# BLOCK7.net
KiCad netlist of a schematic drawn in Altium Designer
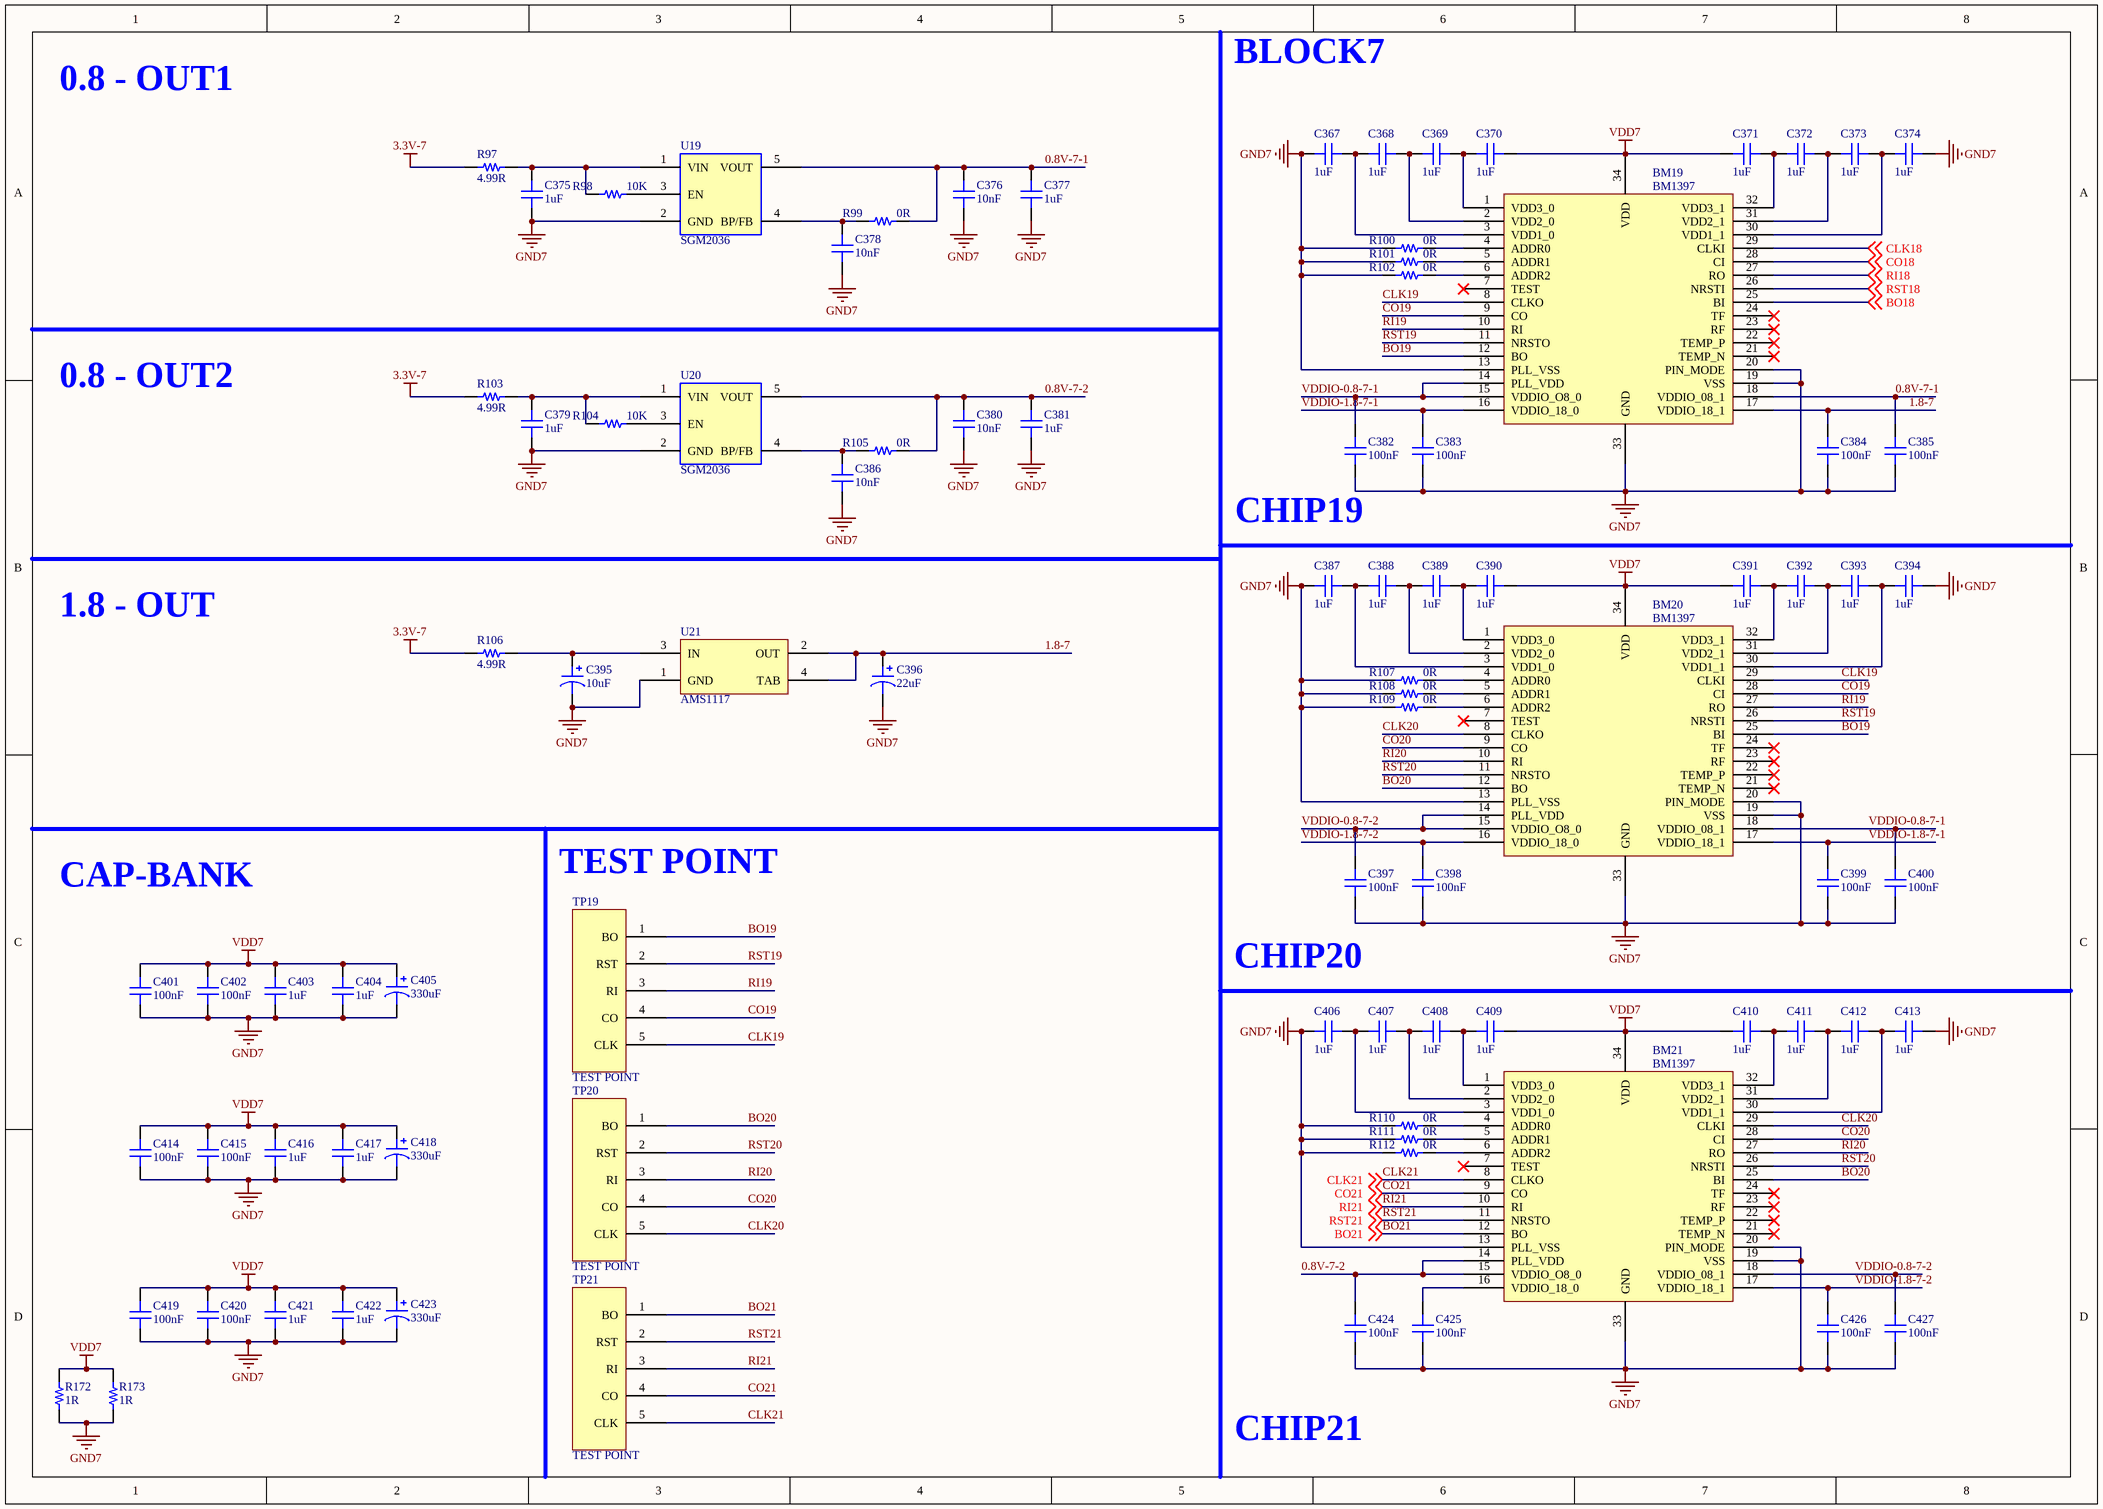
[diagram p0: BLOCK7.SchDoc]

(export (version "E")
  (design (tool "Eeschema 10.0.6"))
  (components
    (comp (ref "BM19") (value "BM1397") (footprint "BM1387") (libsource (lib "Miner_8TH") (part "BM1397_0")))
    (comp (ref "BM20") (value "BM1397") (footprint "BM1387") (libsource (lib "Miner_8TH") (part "BM1397_0")))
    (comp (ref "BM21") (value "BM1397") (footprint "BM1387") (libsource (lib "Miner_8TH") (part "BM1397_0")))
    (comp (ref "C367") (value "1uF") (footprint "CAP-SMD-0603") (libsource (lib "Miner_8TH") (part "CAP")))
    (comp (ref "C368") (value "1uF") (footprint "CAP-SMD-0603") (libsource (lib "Miner_8TH") (part "CAP")))
    (comp (ref "C369") (value "1uF") (footprint "CAP-SMD-0603") (libsource (lib "Miner_8TH") (part "CAP")))
    (comp (ref "C370") (value "1uF") (footprint "CAP-SMD-0603") (libsource (lib "Miner_8TH") (part "CAP")))
    (comp (ref "C371") (value "1uF") (footprint "CAP-SMD-0603") (libsource (lib "Miner_8TH") (part "CAP")))
    (comp (ref "C372") (value "1uF") (footprint "CAP-SMD-0603") (libsource (lib "Miner_8TH") (part "CAP")))
    (comp (ref "C373") (value "1uF") (footprint "CAP-SMD-0603") (libsource (lib "Miner_8TH") (part "CAP")))
    (comp (ref "C374") (value "1uF") (footprint "CAP-SMD-0603") (libsource (lib "Miner_8TH") (part "CAP")))
    (comp (ref "C375") (value "1uF") (footprint "CAP_SMD_0805") (libsource (lib "Miner_8TH") (part "CAP")))
    (comp (ref "C376") (value "10nF") (footprint "CAP_SMD_0805") (libsource (lib "Miner_8TH") (part "CAP")))
    (comp (ref "C377") (value "1uF") (footprint "CAP_SMD_0805") (libsource (lib "Miner_8TH") (part "CAP")))
    (comp (ref "C378") (value "10nF") (footprint "CAP_SMD_0805") (libsource (lib "Miner_8TH") (part "CAP")))
    (comp (ref "C379") (value "1uF") (footprint "CAP_SMD_0805") (libsource (lib "Miner_8TH") (part "CAP")))
    (comp (ref "C380") (value "10nF") (footprint "CAP_SMD_0805") (libsource (lib "Miner_8TH") (part "CAP")))
    (comp (ref "C381") (value "1uF") (footprint "CAP_SMD_0805") (libsource (lib "Miner_8TH") (part "CAP")))
    (comp (ref "C382") (value "100nF") (footprint "CAP_SMD_0805") (libsource (lib "Miner_8TH") (part "CAP")))
    (comp (ref "C383") (value "100nF") (footprint "CAP_SMD_0805") (libsource (lib "Miner_8TH") (part "CAP")))
    (comp (ref "C384") (value "100nF") (footprint "CAP_SMD_0805") (libsource (lib "Miner_8TH") (part "CAP")))
    (comp (ref "C385") (value "100nF") (footprint "CAP_SMD_0805") (libsource (lib "Miner_8TH") (part "CAP")))
    (comp (ref "C386") (value "10nF") (footprint "CAP_SMD_0805") (libsource (lib "Miner_8TH") (part "CAP")))
    (comp (ref "C387") (value "1uF") (footprint "CAP-SMD-0603") (libsource (lib "Miner_8TH") (part "CAP")))
    (comp (ref "C388") (value "1uF") (footprint "CAP-SMD-0603") (libsource (lib "Miner_8TH") (part "CAP")))
    (comp (ref "C389") (value "1uF") (footprint "CAP-SMD-0603") (libsource (lib "Miner_8TH") (part "CAP")))
    (comp (ref "C390") (value "1uF") (footprint "CAP-SMD-0603") (libsource (lib "Miner_8TH") (part "CAP")))
    (comp (ref "C391") (value "1uF") (footprint "CAP-SMD-0603") (libsource (lib "Miner_8TH") (part "CAP")))
    (comp (ref "C392") (value "1uF") (footprint "CAP-SMD-0603") (libsource (lib "Miner_8TH") (part "CAP")))
    (comp (ref "C393") (value "1uF") (footprint "CAP-SMD-0603") (libsource (lib "Miner_8TH") (part "CAP")))
    (comp (ref "C394") (value "1uF") (footprint "CAP-SMD-0603") (libsource (lib "Miner_8TH") (part "CAP")))
    (comp (ref "C395")
      (value "10uF")
      (footprint "CAP-TAN-CASE-A")
      (libsource (lib "Miner_8TH") (part "POLARIZED CAP"))
    )
    (comp (ref "C396")
      (value "22uF")
      (footprint "CAP-TAN-CASE-A")
      (libsource (lib "Miner_8TH") (part "POLARIZED CAP"))
    )
    (comp (ref "C397") (value "100nF") (footprint "CAP_SMD_0805") (libsource (lib "Miner_8TH") (part "CAP")))
    (comp (ref "C398") (value "100nF") (footprint "CAP_SMD_0805") (libsource (lib "Miner_8TH") (part "CAP")))
    (comp (ref "C399") (value "100nF") (footprint "CAP_SMD_0805") (libsource (lib "Miner_8TH") (part "CAP")))
    (comp (ref "C400") (value "100nF") (footprint "CAP_SMD_0805") (libsource (lib "Miner_8TH") (part "CAP")))
    (comp (ref "C401") (value "100nF") (footprint "CAP_SMD_0805") (libsource (lib "Miner_8TH") (part "CAP")))
    (comp (ref "C402") (value "100nF") (footprint "CAP_SMD_0805") (libsource (lib "Miner_8TH") (part "CAP")))
    (comp (ref "C403") (value "1uF") (footprint "CAP_SMD_0805") (libsource (lib "Miner_8TH") (part "CAP")))
    (comp (ref "C404") (value "1uF") (footprint "CAP_SMD_0805") (libsource (lib "Miner_8TH") (part "CAP")))
    (comp (ref "C405")
      (value "330uF")
      (footprint "CAP-TAN-CASE-E")
      (libsource (lib "Miner_8TH") (part "POLARIZED CAP"))
    )
    (comp (ref "C406") (value "1uF") (footprint "CAP-SMD-0603") (libsource (lib "Miner_8TH") (part "CAP")))
    (comp (ref "C407") (value "1uF") (footprint "CAP-SMD-0603") (libsource (lib "Miner_8TH") (part "CAP")))
    (comp (ref "C408") (value "1uF") (footprint "CAP-SMD-0603") (libsource (lib "Miner_8TH") (part "CAP")))
    (comp (ref "C409") (value "1uF") (footprint "CAP-SMD-0603") (libsource (lib "Miner_8TH") (part "CAP")))
    (comp (ref "C410") (value "1uF") (footprint "CAP-SMD-0603") (libsource (lib "Miner_8TH") (part "CAP")))
    (comp (ref "C411") (value "1uF") (footprint "CAP-SMD-0603") (libsource (lib "Miner_8TH") (part "CAP")))
    (comp (ref "C412") (value "1uF") (footprint "CAP-SMD-0603") (libsource (lib "Miner_8TH") (part "CAP")))
    (comp (ref "C413") (value "1uF") (footprint "CAP-SMD-0603") (libsource (lib "Miner_8TH") (part "CAP")))
    (comp (ref "C414") (value "100nF") (footprint "CAP_SMD_0805") (libsource (lib "Miner_8TH") (part "CAP")))
    (comp (ref "C415") (value "100nF") (footprint "CAP_SMD_0805") (libsource (lib "Miner_8TH") (part "CAP")))
    (comp (ref "C416") (value "1uF") (footprint "CAP_SMD_0805") (libsource (lib "Miner_8TH") (part "CAP")))
    (comp (ref "C417") (value "1uF") (footprint "CAP_SMD_0805") (libsource (lib "Miner_8TH") (part "CAP")))
    (comp (ref "C418")
      (value "330uF")
      (footprint "CAP-TAN-CASE-E")
      (libsource (lib "Miner_8TH") (part "POLARIZED CAP"))
    )
    (comp (ref "C419") (value "100nF") (footprint "CAP_SMD_0805") (libsource (lib "Miner_8TH") (part "CAP")))
    (comp (ref "C420") (value "100nF") (footprint "CAP_SMD_0805") (libsource (lib "Miner_8TH") (part "CAP")))
    (comp (ref "C421") (value "1uF") (footprint "CAP_SMD_0805") (libsource (lib "Miner_8TH") (part "CAP")))
    (comp (ref "C422") (value "1uF") (footprint "CAP_SMD_0805") (libsource (lib "Miner_8TH") (part "CAP")))
    (comp (ref "C423")
      (value "330uF")
      (footprint "CAP-TAN-CASE-E")
      (libsource (lib "Miner_8TH") (part "POLARIZED CAP"))
    )
    (comp (ref "C424") (value "100nF") (footprint "CAP_SMD_0805") (libsource (lib "Miner_8TH") (part "CAP")))
    (comp (ref "C425") (value "100nF") (footprint "CAP_SMD_0805") (libsource (lib "Miner_8TH") (part "CAP")))
    (comp (ref "C426") (value "100nF") (footprint "CAP_SMD_0805") (libsource (lib "Miner_8TH") (part "CAP")))
    (comp (ref "C427") (value "100nF") (footprint "CAP_SMD_0805") (libsource (lib "Miner_8TH") (part "CAP")))
    (comp (ref "R97") (value "4.99R") (footprint "RES-SMD-1206") (libsource (lib "Miner_8TH") (part "RES")))
    (comp (ref "R98") (value "10K") (footprint "RES-SMD-0402") (libsource (lib "Miner_8TH") (part "RES")))
    (comp (ref "R99") (value "0R") (footprint "RES-SMD-0402") (libsource (lib "Miner_8TH") (part "RES")))
    (comp (ref "R100") (value "0R") (footprint "RES-SMD-0402") (libsource (lib "Miner_8TH") (part "RES")))
    (comp (ref "R101") (value "0R") (footprint "RES-SMD-0402") (libsource (lib "Miner_8TH") (part "RES")))
    (comp (ref "R102") (value "0R") (footprint "RES-SMD-0402") (libsource (lib "Miner_8TH") (part "RES")))
    (comp (ref "R103") (value "4.99R") (footprint "RES-SMD-1206") (libsource (lib "Miner_8TH") (part "RES")))
    (comp (ref "R104") (value "10K") (footprint "RES-SMD-0402") (libsource (lib "Miner_8TH") (part "RES")))
    (comp (ref "R105") (value "0R") (footprint "RES-SMD-0402") (libsource (lib "Miner_8TH") (part "RES")))
    (comp (ref "R106") (value "4.99R") (footprint "RES-SMD-1206") (libsource (lib "Miner_8TH") (part "RES")))
    (comp (ref "R107") (value "0R") (footprint "RES-SMD-0402") (libsource (lib "Miner_8TH") (part "RES")))
    (comp (ref "R108") (value "0R") (footprint "RES-SMD-0402") (libsource (lib "Miner_8TH") (part "RES")))
    (comp (ref "R109") (value "0R") (footprint "RES-SMD-0402") (libsource (lib "Miner_8TH") (part "RES")))
    (comp (ref "R110") (value "0R") (footprint "RES-SMD-0402") (libsource (lib "Miner_8TH") (part "RES")))
    (comp (ref "R111") (value "0R") (footprint "RES-SMD-0402") (libsource (lib "Miner_8TH") (part "RES")))
    (comp (ref "R112") (value "0R") (footprint "RES-SMD-0402") (libsource (lib "Miner_8TH") (part "RES")))
    (comp (ref "R172") (value "1R") (footprint "RES-SMD-1210") (libsource (lib "Miner_8TH") (part "RES")))
    (comp (ref "R173") (value "1R") (footprint "RES-SMD-1210") (libsource (lib "Miner_8TH") (part "RES")))
    (comp (ref "TP19")
      (value "TEST POINT")
      (footprint "TEST_POINT")
      (libsource (lib "Miner_8TH") (part "TEST POINT"))
    )
    (comp (ref "TP20")
      (value "TEST POINT")
      (footprint "TEST_POINT")
      (libsource (lib "Miner_8TH") (part "TEST POINT"))
    )
    (comp (ref "TP21")
      (value "TEST POINT")
      (footprint "TEST_POINT")
      (libsource (lib "Miner_8TH") (part "TEST POINT"))
    )
    (comp (ref "U19")
      (value "SGM2036")
      (footprint "SOT23-5PIN")
      (libsource (lib "Miner_8TH") (part "SGM2036"))
    )
    (comp (ref "U20")
      (value "SGM2036")
      (footprint "SOT23-5PIN")
      (libsource (lib "Miner_8TH") (part "SGM2036"))
    )
    (comp (ref "U21") (value "AMS1117") (footprint "AMS1117") (libsource (lib "Miner_8TH") (part "AMS1117")))
  )
  (nets
    (net (code "1") (name "/0.8V-7-1") (class "Default")
      (node (ref "BM19") (pin "18") (pinfunction "VDDIO_08_1_18") (pintype "passive"))
      (node (ref "C376") (pin "2") (pinfunction "2_2") (pintype "passive"))
      (node (ref "C377") (pin "2") (pinfunction "2_2") (pintype "passive"))
      (node (ref "C385") (pin "2") (pinfunction "2_2") (pintype "passive"))
      (node (ref "R99") (pin "2") (pinfunction "2_2") (pintype "passive"))
      (node (ref "U19") (pin "5") (pinfunction "VOUT_5") (pintype "passive"))
    )
    (net (code "2") (name "/0.8V-7-2") (class "Default")
      (node (ref "BM21") (pin "14") (pinfunction "PLL_VDD_14") (pintype "passive"))
      (node (ref "BM21") (pin "15") (pinfunction "VDDIO_O8_0_15") (pintype "passive"))
      (node (ref "C380") (pin "2") (pinfunction "2_2") (pintype "passive"))
      (node (ref "C381") (pin "2") (pinfunction "2_2") (pintype "passive"))
      (node (ref "C424") (pin "2") (pinfunction "2_2") (pintype "passive"))
      (node (ref "R105") (pin "2") (pinfunction "2_2") (pintype "passive"))
      (node (ref "U20") (pin "5") (pinfunction "VOUT_5") (pintype "passive"))
    )
    (net (code "3") (name "/1.8-7") (class "Default")
      (node (ref "BM19") (pin "17") (pinfunction "VDDIO_18_1_17") (pintype "passive"))
      (node (ref "C384") (pin "2") (pinfunction "2_2") (pintype "passive"))
      (node (ref "C396") (pin "1") (pinfunction "1_1") (pintype "passive"))
      (node (ref "U21") (pin "2") (pinfunction "OUT_2") (pintype "passive"))
      (node (ref "U21") (pin "4") (pinfunction "TAB_4") (pintype "passive"))
    )
    (net (code "4") (name "/BO19") (class "Default")
      (node (ref "BM19") (pin "12") (pinfunction "BO_12") (pintype "passive"))
      (node (ref "BM20") (pin "25") (pinfunction "BI_25") (pintype "passive"))
      (node (ref "TP19") (pin "1") (pinfunction "BO_1") (pintype "passive"))
    )
    (net (code "5") (name "/BO20") (class "Default")
      (node (ref "BM20") (pin "12") (pinfunction "BO_12") (pintype "passive"))
      (node (ref "BM21") (pin "25") (pinfunction "BI_25") (pintype "passive"))
      (node (ref "TP20") (pin "1") (pinfunction "BO_1") (pintype "passive"))
    )
    (net (code "6") (name "/CLK19") (class "Default")
      (node (ref "BM19") (pin "8") (pinfunction "CLKO_8") (pintype "passive"))
      (node (ref "BM20") (pin "29") (pinfunction "CLKI_29") (pintype "passive"))
      (node (ref "TP19") (pin "5") (pinfunction "CLK_5") (pintype "passive"))
    )
    (net (code "7") (name "/CLK20") (class "Default")
      (node (ref "BM20") (pin "8") (pinfunction "CLKO_8") (pintype "passive"))
      (node (ref "BM21") (pin "29") (pinfunction "CLKI_29") (pintype "passive"))
      (node (ref "TP20") (pin "5") (pinfunction "CLK_5") (pintype "passive"))
    )
    (net (code "8") (name "/CO19") (class "Default")
      (node (ref "BM19") (pin "9") (pinfunction "CO_9") (pintype "passive"))
      (node (ref "BM20") (pin "28") (pinfunction "CI_28") (pintype "passive"))
      (node (ref "TP19") (pin "4") (pinfunction "CO_4") (pintype "passive"))
    )
    (net (code "9") (name "/CO20") (class "Default")
      (node (ref "BM20") (pin "9") (pinfunction "CO_9") (pintype "passive"))
      (node (ref "BM21") (pin "28") (pinfunction "CI_28") (pintype "passive"))
      (node (ref "TP20") (pin "4") (pinfunction "CO_4") (pintype "passive"))
    )
    (net (code "10") (name "/RI19") (class "Default")
      (node (ref "BM19") (pin "10") (pinfunction "RI_10") (pintype "passive"))
      (node (ref "BM20") (pin "27") (pinfunction "RO_27") (pintype "passive"))
      (node (ref "TP19") (pin "3") (pinfunction "RI_3") (pintype "passive"))
    )
    (net (code "11") (name "/RI20") (class "Default")
      (node (ref "BM20") (pin "10") (pinfunction "RI_10") (pintype "passive"))
      (node (ref "BM21") (pin "27") (pinfunction "RO_27") (pintype "passive"))
      (node (ref "TP20") (pin "3") (pinfunction "RI_3") (pintype "passive"))
    )
    (net (code "12") (name "/RST19") (class "Default")
      (node (ref "BM19") (pin "11") (pinfunction "NRSTO_11") (pintype "passive"))
      (node (ref "BM20") (pin "26") (pinfunction "NRSTI_26") (pintype "passive"))
      (node (ref "TP19") (pin "2") (pinfunction "RST_2") (pintype "passive"))
    )
    (net (code "13") (name "/RST20") (class "Default")
      (node (ref "BM20") (pin "11") (pinfunction "NRSTO_11") (pintype "passive"))
      (node (ref "BM21") (pin "26") (pinfunction "NRSTI_26") (pintype "passive"))
      (node (ref "TP20") (pin "2") (pinfunction "RST_2") (pintype "passive"))
    )
    (net (code "14") (name "/VDDIO-0.8-7-1") (class "Default")
      (node (ref "BM19") (pin "14") (pinfunction "PLL_VDD_14") (pintype "passive"))
      (node (ref "BM19") (pin "15") (pinfunction "VDDIO_O8_0_15") (pintype "passive"))
      (node (ref "BM20") (pin "18") (pinfunction "VDDIO_08_1_18") (pintype "passive"))
      (node (ref "C382") (pin "2") (pinfunction "2_2") (pintype "passive"))
      (node (ref "C400") (pin "2") (pinfunction "2_2") (pintype "passive"))
    )
    (net (code "15") (name "/VDDIO-0.8-7-2") (class "Default")
      (node (ref "BM20") (pin "14") (pinfunction "PLL_VDD_14") (pintype "passive"))
      (node (ref "BM20") (pin "15") (pinfunction "VDDIO_O8_0_15") (pintype "passive"))
      (node (ref "BM21") (pin "18") (pinfunction "VDDIO_08_1_18") (pintype "passive"))
      (node (ref "C397") (pin "2") (pinfunction "2_2") (pintype "passive"))
      (node (ref "C427") (pin "2") (pinfunction "2_2") (pintype "passive"))
    )
    (net (code "16") (name "/VDDIO-1.8-7-1") (class "Default")
      (node (ref "BM19") (pin "16") (pinfunction "VDDIO_18_0_16") (pintype "passive"))
      (node (ref "BM20") (pin "17") (pinfunction "VDDIO_18_1_17") (pintype "passive"))
      (node (ref "C383") (pin "2") (pinfunction "2_2") (pintype "passive"))
      (node (ref "C399") (pin "2") (pinfunction "2_2") (pintype "passive"))
    )
    (net (code "17") (name "/VDDIO-1.8-7-2") (class "Default")
      (node (ref "BM20") (pin "16") (pinfunction "VDDIO_18_0_16") (pintype "passive"))
      (node (ref "BM21") (pin "17") (pinfunction "VDDIO_18_1_17") (pintype "passive"))
      (node (ref "C398") (pin "2") (pinfunction "2_2") (pintype "passive"))
      (node (ref "C426") (pin "2") (pinfunction "2_2") (pintype "passive"))
    )
    (net (code "18") (name "3.3V-7") (class "Default")
      (node (ref "R103") (pin "1") (pinfunction "1_1") (pintype "passive"))
      (node (ref "R106") (pin "1") (pinfunction "1_1") (pintype "passive"))
      (node (ref "R97") (pin "1") (pinfunction "1_1") (pintype "passive"))
    )
    (net (code "19") (name "BO18") (class "Default")
      (node (ref "BM19") (pin "25") (pinfunction "BI_25") (pintype "passive"))
    )
    (net (code "20") (name "BO21") (class "Default")
      (node (ref "BM21") (pin "12") (pinfunction "BO_12") (pintype "passive"))
      (node (ref "TP21") (pin "1") (pinfunction "BO_1") (pintype "passive"))
    )
    (net (code "21") (name "CLK18") (class "Default")
      (node (ref "BM19") (pin "29") (pinfunction "CLKI_29") (pintype "passive"))
    )
    (net (code "22") (name "CLK21") (class "Default")
      (node (ref "BM21") (pin "8") (pinfunction "CLKO_8") (pintype "passive"))
      (node (ref "TP21") (pin "5") (pinfunction "CLK_5") (pintype "passive"))
    )
    (net (code "23") (name "CO18") (class "Default")
      (node (ref "BM19") (pin "28") (pinfunction "CI_28") (pintype "passive"))
    )
    (net (code "24") (name "CO21") (class "Default")
      (node (ref "BM21") (pin "9") (pinfunction "CO_9") (pintype "passive"))
      (node (ref "TP21") (pin "4") (pinfunction "CO_4") (pintype "passive"))
    )
    (net (code "25") (name "GND7") (class "Default")
      (node (ref "BM19") (pin "13") (pinfunction "PLL_VSS_13") (pintype "passive"))
      (node (ref "BM19") (pin "19") (pinfunction "VSS_19") (pintype "passive"))
      (node (ref "BM19") (pin "20") (pinfunction "PIN_MODE_20") (pintype "passive"))
      (node (ref "BM19") (pin "33") (pinfunction "GND_33") (pintype "passive"))
      (node (ref "BM20") (pin "13") (pinfunction "PLL_VSS_13") (pintype "passive"))
      (node (ref "BM20") (pin "19") (pinfunction "VSS_19") (pintype "passive"))
      (node (ref "BM20") (pin "20") (pinfunction "PIN_MODE_20") (pintype "passive"))
      (node (ref "BM20") (pin "33") (pinfunction "GND_33") (pintype "passive"))
      (node (ref "BM21") (pin "13") (pinfunction "PLL_VSS_13") (pintype "passive"))
      (node (ref "BM21") (pin "19") (pinfunction "VSS_19") (pintype "passive"))
      (node (ref "BM21") (pin "20") (pinfunction "PIN_MODE_20") (pintype "passive"))
      (node (ref "BM21") (pin "33") (pinfunction "GND_33") (pintype "passive"))
      (node (ref "C367") (pin "1") (pinfunction "1_1") (pintype "passive"))
      (node (ref "C374") (pin "2") (pinfunction "2_2") (pintype "passive"))
      (node (ref "C375") (pin "1") (pinfunction "1_1") (pintype "passive"))
      (node (ref "C376") (pin "1") (pinfunction "1_1") (pintype "passive"))
      (node (ref "C377") (pin "1") (pinfunction "1_1") (pintype "passive"))
      (node (ref "C378") (pin "1") (pinfunction "1_1") (pintype "passive"))
      (node (ref "C379") (pin "1") (pinfunction "1_1") (pintype "passive"))
      (node (ref "C380") (pin "1") (pinfunction "1_1") (pintype "passive"))
      (node (ref "C381") (pin "1") (pinfunction "1_1") (pintype "passive"))
      (node (ref "C382") (pin "1") (pinfunction "1_1") (pintype "passive"))
      (node (ref "C383") (pin "1") (pinfunction "1_1") (pintype "passive"))
      (node (ref "C384") (pin "1") (pinfunction "1_1") (pintype "passive"))
      (node (ref "C385") (pin "1") (pinfunction "1_1") (pintype "passive"))
      (node (ref "C386") (pin "1") (pinfunction "1_1") (pintype "passive"))
      (node (ref "C387") (pin "1") (pinfunction "1_1") (pintype "passive"))
      (node (ref "C394") (pin "2") (pinfunction "2_2") (pintype "passive"))
      (node (ref "C395") (pin "2") (pinfunction "2_2") (pintype "passive"))
      (node (ref "C396") (pin "2") (pinfunction "2_2") (pintype "passive"))
      (node (ref "C397") (pin "1") (pinfunction "1_1") (pintype "passive"))
      (node (ref "C398") (pin "1") (pinfunction "1_1") (pintype "passive"))
      (node (ref "C399") (pin "1") (pinfunction "1_1") (pintype "passive"))
      (node (ref "C400") (pin "1") (pinfunction "1_1") (pintype "passive"))
      (node (ref "C401") (pin "1") (pinfunction "1_1") (pintype "passive"))
      (node (ref "C402") (pin "1") (pinfunction "1_1") (pintype "passive"))
      (node (ref "C403") (pin "1") (pinfunction "1_1") (pintype "passive"))
      (node (ref "C404") (pin "1") (pinfunction "1_1") (pintype "passive"))
      (node (ref "C405") (pin "2") (pinfunction "2_2") (pintype "passive"))
      (node (ref "C406") (pin "1") (pinfunction "1_1") (pintype "passive"))
      (node (ref "C413") (pin "2") (pinfunction "2_2") (pintype "passive"))
      (node (ref "C414") (pin "1") (pinfunction "1_1") (pintype "passive"))
      (node (ref "C415") (pin "1") (pinfunction "1_1") (pintype "passive"))
      (node (ref "C416") (pin "1") (pinfunction "1_1") (pintype "passive"))
      (node (ref "C417") (pin "1") (pinfunction "1_1") (pintype "passive"))
      (node (ref "C418") (pin "2") (pinfunction "2_2") (pintype "passive"))
      (node (ref "C419") (pin "1") (pinfunction "1_1") (pintype "passive"))
      (node (ref "C420") (pin "1") (pinfunction "1_1") (pintype "passive"))
      (node (ref "C421") (pin "1") (pinfunction "1_1") (pintype "passive"))
      (node (ref "C422") (pin "1") (pinfunction "1_1") (pintype "passive"))
      (node (ref "C423") (pin "2") (pinfunction "2_2") (pintype "passive"))
      (node (ref "C424") (pin "1") (pinfunction "1_1") (pintype "passive"))
      (node (ref "C425") (pin "1") (pinfunction "1_1") (pintype "passive"))
      (node (ref "C426") (pin "1") (pinfunction "1_1") (pintype "passive"))
      (node (ref "C427") (pin "1") (pinfunction "1_1") (pintype "passive"))
      (node (ref "R100") (pin "1") (pinfunction "1_1") (pintype "passive"))
      (node (ref "R101") (pin "1") (pinfunction "1_1") (pintype "passive"))
      (node (ref "R102") (pin "1") (pinfunction "1_1") (pintype "passive"))
      (node (ref "R107") (pin "1") (pinfunction "1_1") (pintype "passive"))
      (node (ref "R108") (pin "1") (pinfunction "1_1") (pintype "passive"))
      (node (ref "R109") (pin "1") (pinfunction "1_1") (pintype "passive"))
      (node (ref "R110") (pin "1") (pinfunction "1_1") (pintype "passive"))
      (node (ref "R111") (pin "1") (pinfunction "1_1") (pintype "passive"))
      (node (ref "R112") (pin "1") (pinfunction "1_1") (pintype "passive"))
      (node (ref "R172") (pin "1") (pinfunction "1_1") (pintype "passive"))
      (node (ref "R173") (pin "1") (pinfunction "1_1") (pintype "passive"))
      (node (ref "U19") (pin "2") (pinfunction "GND_2") (pintype "passive"))
      (node (ref "U20") (pin "2") (pinfunction "GND_2") (pintype "passive"))
      (node (ref "U21") (pin "1") (pinfunction "GND_1") (pintype "passive"))
    )
    (net (code "26") (name "Net-(BM19-ADDR0)") (class "Default")
      (node (ref "BM19") (pin "4") (pinfunction "ADDR0_4") (pintype "passive"))
      (node (ref "R100") (pin "2") (pinfunction "2_2") (pintype "passive"))
    )
    (net (code "27") (name "Net-(BM19-ADDR1)") (class "Default")
      (node (ref "BM19") (pin "5") (pinfunction "ADDR1_5") (pintype "passive"))
      (node (ref "R101") (pin "2") (pinfunction "2_2") (pintype "passive"))
    )
    (net (code "28") (name "Net-(BM19-ADDR2)") (class "Default")
      (node (ref "BM19") (pin "6") (pinfunction "ADDR2_6") (pintype "passive"))
      (node (ref "R102") (pin "2") (pinfunction "2_2") (pintype "passive"))
    )
    (net (code "29") (name "Net-(BM19-VDD1_0)") (class "Default")
      (node (ref "BM19") (pin "3") (pinfunction "VDD1_0_3") (pintype "passive"))
      (node (ref "C367") (pin "2") (pinfunction "2_2") (pintype "passive"))
      (node (ref "C368") (pin "1") (pinfunction "1_1") (pintype "passive"))
    )
    (net (code "30") (name "Net-(BM19-VDD1_1)") (class "Default")
      (node (ref "BM19") (pin "30") (pinfunction "VDD1_1_30") (pintype "passive"))
      (node (ref "C373") (pin "2") (pinfunction "2_2") (pintype "passive"))
      (node (ref "C374") (pin "1") (pinfunction "1_1") (pintype "passive"))
    )
    (net (code "31") (name "Net-(BM19-VDD2_0)") (class "Default")
      (node (ref "BM19") (pin "2") (pinfunction "VDD2_0_2") (pintype "passive"))
      (node (ref "C368") (pin "2") (pinfunction "2_2") (pintype "passive"))
      (node (ref "C369") (pin "1") (pinfunction "1_1") (pintype "passive"))
    )
    (net (code "32") (name "Net-(BM19-VDD2_1)") (class "Default")
      (node (ref "BM19") (pin "31") (pinfunction "VDD2_1_31") (pintype "passive"))
      (node (ref "C372") (pin "2") (pinfunction "2_2") (pintype "passive"))
      (node (ref "C373") (pin "1") (pinfunction "1_1") (pintype "passive"))
    )
    (net (code "33") (name "Net-(BM19-VDD3_0)") (class "Default")
      (node (ref "BM19") (pin "1") (pinfunction "VDD3_0_1") (pintype "passive"))
      (node (ref "C369") (pin "2") (pinfunction "2_2") (pintype "passive"))
      (node (ref "C370") (pin "1") (pinfunction "1_1") (pintype "passive"))
    )
    (net (code "34") (name "Net-(BM19-VDD3_1)") (class "Default")
      (node (ref "BM19") (pin "32") (pinfunction "VDD3_1_32") (pintype "passive"))
      (node (ref "C371") (pin "2") (pinfunction "2_2") (pintype "passive"))
      (node (ref "C372") (pin "1") (pinfunction "1_1") (pintype "passive"))
    )
    (net (code "35") (name "Net-(BM20-ADDR0)") (class "Default")
      (node (ref "BM20") (pin "4") (pinfunction "ADDR0_4") (pintype "passive"))
      (node (ref "R107") (pin "2") (pinfunction "2_2") (pintype "passive"))
    )
    (net (code "36") (name "Net-(BM20-ADDR1)") (class "Default")
      (node (ref "BM20") (pin "5") (pinfunction "ADDR1_5") (pintype "passive"))
      (node (ref "R108") (pin "2") (pinfunction "2_2") (pintype "passive"))
    )
    (net (code "37") (name "Net-(BM20-ADDR2)") (class "Default")
      (node (ref "BM20") (pin "6") (pinfunction "ADDR2_6") (pintype "passive"))
      (node (ref "R109") (pin "2") (pinfunction "2_2") (pintype "passive"))
    )
    (net (code "38") (name "Net-(BM20-VDD1_0)") (class "Default")
      (node (ref "BM20") (pin "3") (pinfunction "VDD1_0_3") (pintype "passive"))
      (node (ref "C387") (pin "2") (pinfunction "2_2") (pintype "passive"))
      (node (ref "C388") (pin "1") (pinfunction "1_1") (pintype "passive"))
    )
    (net (code "39") (name "Net-(BM20-VDD1_1)") (class "Default")
      (node (ref "BM20") (pin "30") (pinfunction "VDD1_1_30") (pintype "passive"))
      (node (ref "C393") (pin "2") (pinfunction "2_2") (pintype "passive"))
      (node (ref "C394") (pin "1") (pinfunction "1_1") (pintype "passive"))
    )
    (net (code "40") (name "Net-(BM20-VDD2_0)") (class "Default")
      (node (ref "BM20") (pin "2") (pinfunction "VDD2_0_2") (pintype "passive"))
      (node (ref "C388") (pin "2") (pinfunction "2_2") (pintype "passive"))
      (node (ref "C389") (pin "1") (pinfunction "1_1") (pintype "passive"))
    )
    (net (code "41") (name "Net-(BM20-VDD2_1)") (class "Default")
      (node (ref "BM20") (pin "31") (pinfunction "VDD2_1_31") (pintype "passive"))
      (node (ref "C392") (pin "2") (pinfunction "2_2") (pintype "passive"))
      (node (ref "C393") (pin "1") (pinfunction "1_1") (pintype "passive"))
    )
    (net (code "42") (name "Net-(BM20-VDD3_0)") (class "Default")
      (node (ref "BM20") (pin "1") (pinfunction "VDD3_0_1") (pintype "passive"))
      (node (ref "C389") (pin "2") (pinfunction "2_2") (pintype "passive"))
      (node (ref "C390") (pin "1") (pinfunction "1_1") (pintype "passive"))
    )
    (net (code "43") (name "Net-(BM20-VDD3_1)") (class "Default")
      (node (ref "BM20") (pin "32") (pinfunction "VDD3_1_32") (pintype "passive"))
      (node (ref "C391") (pin "2") (pinfunction "2_2") (pintype "passive"))
      (node (ref "C392") (pin "1") (pinfunction "1_1") (pintype "passive"))
    )
    (net (code "44") (name "Net-(BM21-ADDR0)") (class "Default")
      (node (ref "BM21") (pin "4") (pinfunction "ADDR0_4") (pintype "passive"))
      (node (ref "R110") (pin "2") (pinfunction "2_2") (pintype "passive"))
    )
    (net (code "45") (name "Net-(BM21-ADDR1)") (class "Default")
      (node (ref "BM21") (pin "5") (pinfunction "ADDR1_5") (pintype "passive"))
      (node (ref "R111") (pin "2") (pinfunction "2_2") (pintype "passive"))
    )
    (net (code "46") (name "Net-(BM21-ADDR2)") (class "Default")
      (node (ref "BM21") (pin "6") (pinfunction "ADDR2_6") (pintype "passive"))
      (node (ref "R112") (pin "2") (pinfunction "2_2") (pintype "passive"))
    )
    (net (code "47") (name "Net-(BM21-VDD1_0)") (class "Default")
      (node (ref "BM21") (pin "3") (pinfunction "VDD1_0_3") (pintype "passive"))
      (node (ref "C406") (pin "2") (pinfunction "2_2") (pintype "passive"))
      (node (ref "C407") (pin "1") (pinfunction "1_1") (pintype "passive"))
    )
    (net (code "48") (name "Net-(BM21-VDD1_1)") (class "Default")
      (node (ref "BM21") (pin "30") (pinfunction "VDD1_1_30") (pintype "passive"))
      (node (ref "C412") (pin "2") (pinfunction "2_2") (pintype "passive"))
      (node (ref "C413") (pin "1") (pinfunction "1_1") (pintype "passive"))
    )
    (net (code "49") (name "Net-(BM21-VDD2_0)") (class "Default")
      (node (ref "BM21") (pin "2") (pinfunction "VDD2_0_2") (pintype "passive"))
      (node (ref "C407") (pin "2") (pinfunction "2_2") (pintype "passive"))
      (node (ref "C408") (pin "1") (pinfunction "1_1") (pintype "passive"))
    )
    (net (code "50") (name "Net-(BM21-VDD2_1)") (class "Default")
      (node (ref "BM21") (pin "31") (pinfunction "VDD2_1_31") (pintype "passive"))
      (node (ref "C411") (pin "2") (pinfunction "2_2") (pintype "passive"))
      (node (ref "C412") (pin "1") (pinfunction "1_1") (pintype "passive"))
    )
    (net (code "51") (name "Net-(BM21-VDD3_0)") (class "Default")
      (node (ref "BM21") (pin "1") (pinfunction "VDD3_0_1") (pintype "passive"))
      (node (ref "C408") (pin "2") (pinfunction "2_2") (pintype "passive"))
      (node (ref "C409") (pin "1") (pinfunction "1_1") (pintype "passive"))
    )
    (net (code "52") (name "Net-(BM21-VDD3_1)") (class "Default")
      (node (ref "BM21") (pin "32") (pinfunction "VDD3_1_32") (pintype "passive"))
      (node (ref "C410") (pin "2") (pinfunction "2_2") (pintype "passive"))
      (node (ref "C411") (pin "1") (pinfunction "1_1") (pintype "passive"))
    )
    (net (code "53") (name "Net-(BM21-VDDIO_18_0)") (class "Default")
      (node (ref "BM21") (pin "16") (pinfunction "VDDIO_18_0_16") (pintype "passive"))
      (node (ref "C425") (pin "2") (pinfunction "2_2") (pintype "passive"))
    )
    (net (code "54") (name "Net-(U19-BP{slash}FB)") (class "Default")
      (node (ref "C378") (pin "2") (pinfunction "2_2") (pintype "passive"))
      (node (ref "R99") (pin "1") (pinfunction "1_1") (pintype "passive"))
      (node (ref "U19") (pin "4") (pinfunction "BP/FB_4") (pintype "passive"))
    )
    (net (code "55") (name "Net-(U19-EN)") (class "Default")
      (node (ref "R98") (pin "2") (pinfunction "2_2") (pintype "passive"))
      (node (ref "U19") (pin "3") (pinfunction "EN_3") (pintype "passive"))
    )
    (net (code "56") (name "Net-(U19-VIN)") (class "Default")
      (node (ref "C375") (pin "2") (pinfunction "2_2") (pintype "passive"))
      (node (ref "R97") (pin "2") (pinfunction "2_2") (pintype "passive"))
      (node (ref "R98") (pin "1") (pinfunction "1_1") (pintype "passive"))
      (node (ref "U19") (pin "1") (pinfunction "VIN_1") (pintype "passive"))
    )
    (net (code "57") (name "Net-(U20-BP{slash}FB)") (class "Default")
      (node (ref "C386") (pin "2") (pinfunction "2_2") (pintype "passive"))
      (node (ref "R105") (pin "1") (pinfunction "1_1") (pintype "passive"))
      (node (ref "U20") (pin "4") (pinfunction "BP/FB_4") (pintype "passive"))
    )
    (net (code "58") (name "Net-(U20-EN)") (class "Default")
      (node (ref "R104") (pin "2") (pinfunction "2_2") (pintype "passive"))
      (node (ref "U20") (pin "3") (pinfunction "EN_3") (pintype "passive"))
    )
    (net (code "59") (name "Net-(U20-VIN)") (class "Default")
      (node (ref "C379") (pin "2") (pinfunction "2_2") (pintype "passive"))
      (node (ref "R103") (pin "2") (pinfunction "2_2") (pintype "passive"))
      (node (ref "R104") (pin "1") (pinfunction "1_1") (pintype "passive"))
      (node (ref "U20") (pin "1") (pinfunction "VIN_1") (pintype "passive"))
    )
    (net (code "60") (name "Net-(U21-IN)") (class "Default")
      (node (ref "C395") (pin "1") (pinfunction "1_1") (pintype "passive"))
      (node (ref "R106") (pin "2") (pinfunction "2_2") (pintype "passive"))
      (node (ref "U21") (pin "3") (pinfunction "IN_3") (pintype "passive"))
    )
    (net (code "61") (name "RI18") (class "Default")
      (node (ref "BM19") (pin "27") (pinfunction "RO_27") (pintype "passive"))
    )
    (net (code "62") (name "RI21") (class "Default")
      (node (ref "BM21") (pin "10") (pinfunction "RI_10") (pintype "passive"))
      (node (ref "TP21") (pin "3") (pinfunction "RI_3") (pintype "passive"))
    )
    (net (code "63") (name "RST18") (class "Default")
      (node (ref "BM19") (pin "26") (pinfunction "NRSTI_26") (pintype "passive"))
    )
    (net (code "64") (name "RST21") (class "Default")
      (node (ref "BM21") (pin "11") (pinfunction "NRSTO_11") (pintype "passive"))
      (node (ref "TP21") (pin "2") (pinfunction "RST_2") (pintype "passive"))
    )
    (net (code "65") (name "VDD7") (class "Default")
      (node (ref "BM19") (pin "34") (pinfunction "VDD_34") (pintype "passive"))
      (node (ref "BM20") (pin "34") (pinfunction "VDD_34") (pintype "passive"))
      (node (ref "BM21") (pin "34") (pinfunction "VDD_34") (pintype "passive"))
      (node (ref "C370") (pin "2") (pinfunction "2_2") (pintype "passive"))
      (node (ref "C371") (pin "1") (pinfunction "1_1") (pintype "passive"))
      (node (ref "C390") (pin "2") (pinfunction "2_2") (pintype "passive"))
      (node (ref "C391") (pin "1") (pinfunction "1_1") (pintype "passive"))
      (node (ref "C401") (pin "2") (pinfunction "2_2") (pintype "passive"))
      (node (ref "C402") (pin "2") (pinfunction "2_2") (pintype "passive"))
      (node (ref "C403") (pin "2") (pinfunction "2_2") (pintype "passive"))
      (node (ref "C404") (pin "2") (pinfunction "2_2") (pintype "passive"))
      (node (ref "C405") (pin "1") (pinfunction "1_1") (pintype "passive"))
      (node (ref "C409") (pin "2") (pinfunction "2_2") (pintype "passive"))
      (node (ref "C410") (pin "1") (pinfunction "1_1") (pintype "passive"))
      (node (ref "C414") (pin "2") (pinfunction "2_2") (pintype "passive"))
      (node (ref "C415") (pin "2") (pinfunction "2_2") (pintype "passive"))
      (node (ref "C416") (pin "2") (pinfunction "2_2") (pintype "passive"))
      (node (ref "C417") (pin "2") (pinfunction "2_2") (pintype "passive"))
      (node (ref "C418") (pin "1") (pinfunction "1_1") (pintype "passive"))
      (node (ref "C419") (pin "2") (pinfunction "2_2") (pintype "passive"))
      (node (ref "C420") (pin "2") (pinfunction "2_2") (pintype "passive"))
      (node (ref "C421") (pin "2") (pinfunction "2_2") (pintype "passive"))
      (node (ref "C422") (pin "2") (pinfunction "2_2") (pintype "passive"))
      (node (ref "C423") (pin "1") (pinfunction "1_1") (pintype "passive"))
      (node (ref "R172") (pin "2") (pinfunction "2_2") (pintype "passive"))
      (node (ref "R173") (pin "2") (pinfunction "2_2") (pintype "passive"))
    )
    (net (code "66") (name "unconnected-(BM19-RF-Pad23)") (class "Default")
      (node (ref "BM19") (pin "23") (pinfunction "RF_23") (pintype "passive+no_connect"))
    )
    (net (code "67") (name "unconnected-(BM19-TEMP_N-Pad21)") (class "Default")
      (node (ref "BM19") (pin "21") (pinfunction "TEMP_N_21") (pintype "passive+no_connect"))
    )
    (net (code "68") (name "unconnected-(BM19-TEMP_P-Pad22)") (class "Default")
      (node (ref "BM19") (pin "22") (pinfunction "TEMP_P_22") (pintype "passive+no_connect"))
    )
    (net (code "69") (name "unconnected-(BM19-TEST-Pad7)") (class "Default")
      (node (ref "BM19") (pin "7") (pinfunction "TEST_7") (pintype "passive+no_connect"))
    )
    (net (code "70") (name "unconnected-(BM19-TF-Pad24)") (class "Default")
      (node (ref "BM19") (pin "24") (pinfunction "TF_24") (pintype "passive+no_connect"))
    )
    (net (code "71") (name "unconnected-(BM20-RF-Pad23)") (class "Default")
      (node (ref "BM20") (pin "23") (pinfunction "RF_23") (pintype "passive+no_connect"))
    )
    (net (code "72") (name "unconnected-(BM20-TEMP_N-Pad21)") (class "Default")
      (node (ref "BM20") (pin "21") (pinfunction "TEMP_N_21") (pintype "passive+no_connect"))
    )
    (net (code "73") (name "unconnected-(BM20-TEMP_P-Pad22)") (class "Default")
      (node (ref "BM20") (pin "22") (pinfunction "TEMP_P_22") (pintype "passive+no_connect"))
    )
    (net (code "74") (name "unconnected-(BM20-TEST-Pad7)") (class "Default")
      (node (ref "BM20") (pin "7") (pinfunction "TEST_7") (pintype "passive+no_connect"))
    )
    (net (code "75") (name "unconnected-(BM20-TF-Pad24)") (class "Default")
      (node (ref "BM20") (pin "24") (pinfunction "TF_24") (pintype "passive+no_connect"))
    )
    (net (code "76") (name "unconnected-(BM21-RF-Pad23)") (class "Default")
      (node (ref "BM21") (pin "23") (pinfunction "RF_23") (pintype "passive+no_connect"))
    )
    (net (code "77") (name "unconnected-(BM21-TEMP_N-Pad21)") (class "Default")
      (node (ref "BM21") (pin "21") (pinfunction "TEMP_N_21") (pintype "passive+no_connect"))
    )
    (net (code "78") (name "unconnected-(BM21-TEMP_P-Pad22)") (class "Default")
      (node (ref "BM21") (pin "22") (pinfunction "TEMP_P_22") (pintype "passive+no_connect"))
    )
    (net (code "79") (name "unconnected-(BM21-TEST-Pad7)") (class "Default")
      (node (ref "BM21") (pin "7") (pinfunction "TEST_7") (pintype "passive+no_connect"))
    )
    (net (code "80") (name "unconnected-(BM21-TF-Pad24)") (class "Default")
      (node (ref "BM21") (pin "24") (pinfunction "TF_24") (pintype "passive+no_connect"))
    )
  )
)
